# led.net
KiCad netlist of a schematic drawn in Altium Designer
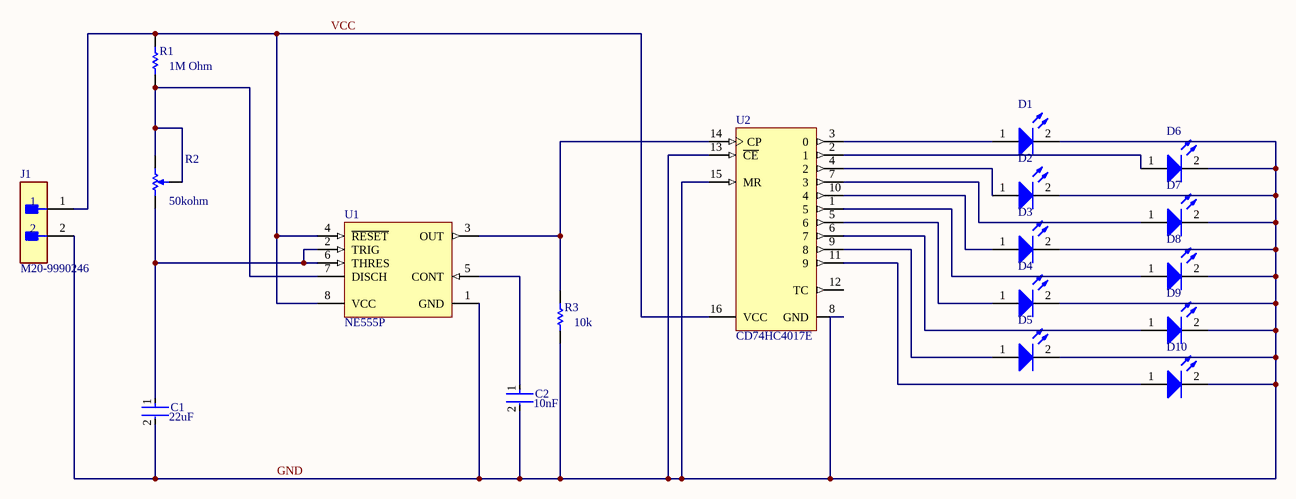
[diagram p0: led.SchDoc]

(export (version "E")
  (design (tool "Eeschema 10.0.6"))
  (components
    (comp (ref "C1")
      (value "RCER71E226MWM1H03A")
      (footprint "FP-RCEWM1-MFG")
      (description "CAP CER 22UF 25V X7R RADIAL")
      (fields (field (name "CAPACITANCE") "22uF") (field (name "TOLERANCE") "20%"))
      (libsource (lib "Altium Content Vault") (part "02cd4be3c70576c341d710602a673aa"))
    )
    (comp (ref "C2")
      (value "RCER71H103K0K1H03B")
      (footprint "FP-RCE0K1-MFG")
      (description "Cap Ceramic 10nF 50V X7R ±10% Radial 5mm +125°C Automotive Bulk")
      (fields (field (name "CAPACITANCE") "10nF") (field (name "TOLERANCE") "10%"))
      (libsource (lib "Altium Content Vault") (part "b4654b650e69147ec39a6b967a45e02"))
    )
    (comp (ref "D1")
      (value "151051BS04000")
      (footprint "WL-TMRC_D5.9H8.7")
      (libsource (lib "Altium Content Vault") (part "LED_Blue_1A-2K"))
    )
    (comp (ref "D2")
      (value "151051BS04000")
      (footprint "WL-TMRC_D5.9H8.7")
      (libsource (lib "Altium Content Vault") (part "LED_Blue_1A-2K"))
    )
    (comp (ref "D3")
      (value "151051BS04000")
      (footprint "WL-TMRC_D5.9H8.7")
      (libsource (lib "Altium Content Vault") (part "LED_Blue_1A-2K"))
    )
    (comp (ref "D4")
      (value "151051BS04000")
      (footprint "WL-TMRC_D5.9H8.7")
      (libsource (lib "Altium Content Vault") (part "LED_Blue_1A-2K"))
    )
    (comp (ref "D5")
      (value "151051BS04000")
      (footprint "WL-TMRC_D5.9H8.7")
      (libsource (lib "Altium Content Vault") (part "LED_Blue_1A-2K"))
    )
    (comp (ref "D6")
      (value "151051BS04000")
      (footprint "WL-TMRC_D5.9H8.7")
      (libsource (lib "Altium Content Vault") (part "LED_Blue_1A-2K"))
    )
    (comp (ref "D7")
      (value "151051BS04000")
      (footprint "WL-TMRC_D5.9H8.7")
      (libsource (lib "Altium Content Vault") (part "LED_Blue_1A-2K"))
    )
    (comp (ref "D8")
      (value "151051BS04000")
      (footprint "WL-TMRC_D5.9H8.7")
      (libsource (lib "Altium Content Vault") (part "LED_Blue_1A-2K"))
    )
    (comp (ref "D9")
      (value "151051BS04000")
      (footprint "WL-TMRC_D5.9H8.7")
      (libsource (lib "Altium Content Vault") (part "LED_Blue_1A-2K"))
    )
    (comp (ref "D10")
      (value "151051BS04000")
      (footprint "WL-TMRC_D5.9H8.7")
      (libsource (lib "Altium Content Vault") (part "LED_Blue_1A-2K"))
    )
    (comp (ref "J1")
      (value "M20-9990246")
      (footprint "FP-M20-9990246-MFG")
      (description "Connector Header Through Hole 2 position 0.100\" (2.54mm)")
      (fields (field (name "OCTOPART") "https://octopart.com/m20-9990246-harwin-2590635"))
      (libsource (lib "Altium Content Vault") (part "3bc925449376181038e59eaffc5286c"))
    )
    (comp (ref "R1")
      (value "MFR-25FBF52-1M")
      (footprint "RESA60-630X240")
      (description "Axial Resistor, 1 MOhm, +/- 1%, 250 mW, -55 to 155 degC, 2-Pin THD, RoHS, Bulk")
      (fields (field (name "RESISTANCE") "1M Ohm") (field (name "TOLERANCE") "1%"))
      (libsource (lib "Altium Content Vault") (part "RES-2"))
    )
    (comp (ref "R2")
      (value "3313J-1-503E")
      (footprint "BOUR-3313J-1_V")
      (fields (field (name "MANUFACTURER") "Bourns") (field (name "TRACK RESISTANCE") "50kohm"))
      (libsource (lib "Altium Content Vault") (part "RES-ADJ-3_A"))
    )
    (comp (ref "R3")
      (value "OD103JE")
      (footprint "OMTE-RES7X2.5-2")
      (fields
        (field (name "RESISTANCE (OHMS)") "10k")
        (field (name "TOLERANCE") "±5%")
        (field (name "MANUFACTURER") "Ohmite")
      )
      (libsource (lib "Altium Content Vault") (part "RES-2"))
    )
    (comp (ref "U1")
      (value "NE555P")
      (footprint "P0008A")
      (description "Precision Timer, 4.5 to 16 V, 0 to 70 degC, 8-Pin DIP, Pb-Free, Tube")
      (fields (field (name "MANUFACTURER") "TexasInstruments"))
      (libsource (lib "Altium Content Vault") (part "TI-NE555-P8"))
    )
    (comp (ref "U2")
      (value "CD74HC4017E")
      (footprint "N0016A")
      (description "High Speed CMOS Logic Decade Counter/Divider with 10 Decoded Outputs, N0016A, TUBE")
      (fields
        (field (name "GENERIC PART NUMBER") "CD74HC4017")
        (field (name "MANUFACTURER") "Texas Instruments")
      )
      (libsource (lib "Altium Content Vault") (part "TI-CD74HC4017-16"))
    )
  )
  (nets
    (net (code "1") (name "/GND") (class "Default")
      (node (ref "C1") (pin "2") (pinfunction "2_2") (pintype "passive"))
      (node (ref "C2") (pin "2") (pinfunction "2_2") (pintype "passive"))
      (node (ref "D1") (pin "2") (pinfunction "K_2") (pintype "passive"))
      (node (ref "D10") (pin "2") (pinfunction "K_2") (pintype "passive"))
      (node (ref "D2") (pin "2") (pinfunction "K_2") (pintype "passive"))
      (node (ref "D3") (pin "2") (pinfunction "K_2") (pintype "passive"))
      (node (ref "D4") (pin "2") (pinfunction "K_2") (pintype "passive"))
      (node (ref "D5") (pin "2") (pinfunction "K_2") (pintype "passive"))
      (node (ref "D6") (pin "2") (pinfunction "K_2") (pintype "passive"))
      (node (ref "D7") (pin "2") (pinfunction "K_2") (pintype "passive"))
      (node (ref "D8") (pin "2") (pinfunction "K_2") (pintype "passive"))
      (node (ref "D9") (pin "2") (pinfunction "K_2") (pintype "passive"))
      (node (ref "J1") (pin "2") (pinfunction "2_2") (pintype "passive"))
      (node (ref "R3") (pin "1") (pinfunction "1_1") (pintype "passive"))
      (node (ref "U1") (pin "1") (pinfunction "GND_1") (pintype "power_in"))
      (node (ref "U2") (pin "13") (pinfunction "~{CE}_13") (pintype "input"))
      (node (ref "U2") (pin "15") (pinfunction "MR_15") (pintype "input"))
      (node (ref "U2") (pin "8") (pinfunction "GND_8") (pintype "power_in"))
    )
    (net (code "2") (name "/VCC") (class "Default")
      (node (ref "J1") (pin "1") (pinfunction "1_1") (pintype "passive"))
      (node (ref "R1") (pin "2") (pinfunction "2_2") (pintype "passive"))
      (node (ref "U1") (pin "4") (pinfunction "~{RESET}_4") (pintype "input"))
      (node (ref "U1") (pin "8") (pinfunction "VCC_8") (pintype "power_in"))
      (node (ref "U2") (pin "16") (pinfunction "VCC_16") (pintype "power_in"))
    )
    (net (code "3") (name "Net-(D1-A)") (class "Default")
      (node (ref "D1") (pin "1") (pinfunction "A_1") (pintype "passive"))
      (node (ref "U2") (pin "3") (pinfunction "0_3") (pintype "output"))
    )
    (net (code "4") (name "Net-(D2-A)") (class "Default")
      (node (ref "D2") (pin "1") (pinfunction "A_1") (pintype "passive"))
      (node (ref "U2") (pin "4") (pinfunction "2_4") (pintype "output"))
    )
    (net (code "5") (name "Net-(D3-A)") (class "Default")
      (node (ref "D3") (pin "1") (pinfunction "A_1") (pintype "passive"))
      (node (ref "U2") (pin "10") (pinfunction "4_10") (pintype "output"))
    )
    (net (code "6") (name "Net-(D4-A)") (class "Default")
      (node (ref "D4") (pin "1") (pinfunction "A_1") (pintype "passive"))
      (node (ref "U2") (pin "5") (pinfunction "6_5") (pintype "output"))
    )
    (net (code "7") (name "Net-(D5-A)") (class "Default")
      (node (ref "D5") (pin "1") (pinfunction "A_1") (pintype "passive"))
      (node (ref "U2") (pin "9") (pinfunction "8_9") (pintype "output"))
    )
    (net (code "8") (name "Net-(D6-A)") (class "Default")
      (node (ref "D6") (pin "1") (pinfunction "A_1") (pintype "passive"))
      (node (ref "U2") (pin "2") (pinfunction "1_2") (pintype "output"))
    )
    (net (code "9") (name "Net-(D7-A)") (class "Default")
      (node (ref "D7") (pin "1") (pinfunction "A_1") (pintype "passive"))
      (node (ref "U2") (pin "7") (pinfunction "3_7") (pintype "output"))
    )
    (net (code "10") (name "Net-(D8-A)") (class "Default")
      (node (ref "D8") (pin "1") (pinfunction "A_1") (pintype "passive"))
      (node (ref "U2") (pin "1") (pinfunction "5_1") (pintype "output"))
    )
    (net (code "11") (name "Net-(D9-A)") (class "Default")
      (node (ref "D9") (pin "1") (pinfunction "A_1") (pintype "passive"))
      (node (ref "U2") (pin "6") (pinfunction "7_6") (pintype "output"))
    )
    (net (code "12") (name "Net-(D10-A)") (class "Default")
      (node (ref "D10") (pin "1") (pinfunction "A_1") (pintype "passive"))
      (node (ref "U2") (pin "11") (pinfunction "9_11") (pintype "output"))
    )
    (net (code "13") (name "Net-(U1-CONT)") (class "Default")
      (node (ref "C2") (pin "1") (pinfunction "1_1") (pintype "passive"))
      (node (ref "U1") (pin "5") (pinfunction "CONT_5") (pintype "input"))
    )
    (net (code "14") (name "Net-(U1-DISCH)") (class "Default")
      (node (ref "R1") (pin "1") (pinfunction "1_1") (pintype "passive"))
      (node (ref "R2") (pin "2") (pinfunction "2_2") (pintype "passive"))
      (node (ref "R2") (pin "3") (pinfunction "3_3") (pintype "passive"))
      (node (ref "U1") (pin "7") (pinfunction "DISCH_7") (pintype "open_collector"))
    )
    (net (code "15") (name "Net-(U1-OUT)") (class "Default")
      (node (ref "R3") (pin "2") (pinfunction "2_2") (pintype "passive"))
      (node (ref "U1") (pin "3") (pinfunction "OUT_3") (pintype "output"))
      (node (ref "U2") (pin "14") (pinfunction "CP_14") (pintype "input"))
    )
    (net (code "16") (name "Net-(U1-THRES)") (class "Default")
      (node (ref "C1") (pin "1") (pinfunction "1_1") (pintype "passive"))
      (node (ref "R2") (pin "1") (pinfunction "1_1") (pintype "passive"))
      (node (ref "U1") (pin "2") (pinfunction "TRIG_2") (pintype "input"))
      (node (ref "U1") (pin "6") (pinfunction "THRES_6") (pintype "input"))
    )
    (net (code "17") (name "unconnected-(U2-TC-Pad12)") (class "Default")
      (node (ref "U2") (pin "12") (pinfunction "TC_12") (pintype "output"))
    )
  )
)
